# Power_w_tantalum.net
KiCad netlist of a schematic drawn in Altium Designer
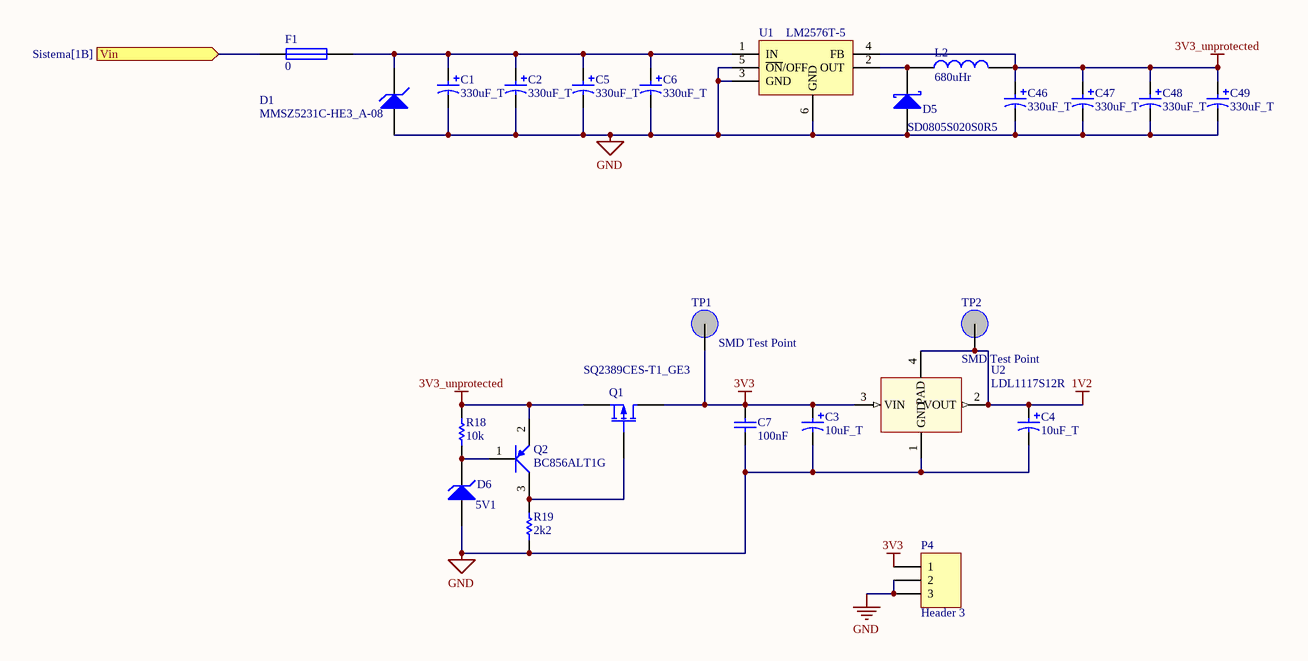
[diagram p0: Power_w_tantalum.SchDoc]

(export (version "E")
  (design (tool "Eeschema 10.0.6"))
  (components
    (comp (ref "C1")
      (value "330uF_T")
      (footprint "C_2917")
      (description "Capacitor SMD 2917 Tant")
      (fields
        (field (name "MANUFACTURER") "Vishay")
        (field (name "MANUFACTURER PART NUMBER") "TMCP1A106MTRF")
      )
      (libsource (lib "Mi_lib") (part "C_330uF_tant_16V"))
    )
    (comp (ref "C2")
      (value "330uF_T")
      (footprint "C_2917")
      (description "Capacitor SMD 2917 Tant")
      (fields
        (field (name "MANUFACTURER") "Vishay")
        (field (name "MANUFACTURER PART NUMBER") "TMCP1A106MTRF")
      )
      (libsource (lib "Mi_lib") (part "C_330uF_tant_16V"))
    )
    (comp (ref "C3")
      (value "10uF_T")
      (footprint "C_0805_2013_c")
      (description "Capacitor SMD 0805 Tant")
      (fields
        (field (name "MANUFACTURER") "Vishay")
        (field (name "MANUFACTURER PART NUMBER") "TMCP1A106MTRF")
      )
      (libsource (lib "MyLibraryV2") (part "C_10uF_10V_b"))
    )
    (comp (ref "C4")
      (value "10uF_T")
      (footprint "C_0805_2013_c")
      (description "Capacitor SMD 0805 Tant")
      (fields
        (field (name "MANUFACTURER") "Vishay")
        (field (name "MANUFACTURER PART NUMBER") "TMCP1A106MTRF")
      )
      (libsource (lib "MyLibraryV2") (part "C_10uF_10V_b"))
    )
    (comp (ref "C5")
      (value "330uF_T")
      (footprint "C_2917")
      (description "Capacitor SMD 2917 Tant")
      (fields
        (field (name "MANUFACTURER") "Vishay")
        (field (name "MANUFACTURER PART NUMBER") "TMCP1A106MTRF")
      )
      (libsource (lib "Mi_lib") (part "C_330uF_tant_16V"))
    )
    (comp (ref "C6")
      (value "330uF_T")
      (footprint "C_2917")
      (description "Capacitor SMD 2917 Tant")
      (fields
        (field (name "MANUFACTURER") "Vishay")
        (field (name "MANUFACTURER PART NUMBER") "TMCP1A106MTRF")
      )
      (libsource (lib "Mi_lib") (part "C_330uF_tant_16V"))
    )
    (comp (ref "C7")
      (value "100nF")
      (footprint "C_0805_2013_b")
      (description "Capacitor SMD 0805")
      (fields (field (name "TOLERANCE") "10%") (field (name "VOLTAGE") "50V"))
      (libsource (lib "MyLibraryV2") (part "C_100nF_50V_b"))
    )
    (comp (ref "C46")
      (value "330uF_T")
      (footprint "C_2917")
      (description "Capacitor SMD 2917 Tant")
      (fields
        (field (name "MANUFACTURER") "Vishay")
        (field (name "MANUFACTURER PART NUMBER") "TMCP1A106MTRF")
      )
      (libsource (lib "Mi_lib") (part "C_330uF_tant_16V"))
    )
    (comp (ref "C47")
      (value "330uF_T")
      (footprint "C_2917")
      (description "Capacitor SMD 2917 Tant")
      (fields
        (field (name "MANUFACTURER") "Vishay")
        (field (name "MANUFACTURER PART NUMBER") "TMCP1A106MTRF")
      )
      (libsource (lib "Mi_lib") (part "C_330uF_tant_16V"))
    )
    (comp (ref "C48")
      (value "330uF_T")
      (footprint "C_2917")
      (description "Capacitor SMD 2917 Tant")
      (fields
        (field (name "MANUFACTURER") "Vishay")
        (field (name "MANUFACTURER PART NUMBER") "TMCP1A106MTRF")
      )
      (libsource (lib "Mi_lib") (part "C_330uF_tant_16V"))
    )
    (comp (ref "C49")
      (value "330uF_T")
      (footprint "C_2917")
      (description "Capacitor SMD 2917 Tant")
      (fields
        (field (name "MANUFACTURER") "Vishay")
        (field (name "MANUFACTURER PART NUMBER") "TMCP1A106MTRF")
      )
      (libsource (lib "Mi_lib") (part "C_330uF_tant_16V"))
    )
    (comp (ref "D1")
      (value "MMSZ5231C-HE3_A-08")
      (footprint "D_SOD-123")
      (description "Diode SMD SOD-123 Zener 5V1")
      (fields (field (name "TOLERANCE") "2%") (field (name "MANUFACTURER") "Vishay Semiconductors"))
      (libsource (lib "Mi_lib") (part "D_MMSZ5231C-HE3_A-08"))
    )
    (comp (ref "D5")
      (value "SD0805S020S0R5")
      (footprint "D_SOD-123")
      (description "Diode SMD D_SD0805S020S0R5")
      (fields (field (name "MANUFACTURER") "Diodes") (field (name "MANUFACTURER PART NUMBER") "B550C-13-F"))
      (libsource (lib "Mi_lib") (part "D_SD0805S020S0R5"))
    )
    (comp (ref "D6")
      (value "5V1")
      (footprint "D_SOD-123")
      (description "Zener Diode")
      (fields (field (name "TOLERANCE") "3%") (field (name "MANUFACTURER") "Diodes"))
      (libsource (lib "MyLibraryV2") (part "D_DDZ5V1B-7"))
    )
    (comp (ref "F1")
      (value "0")
      (footprint "F_0805_2012")
      (description "(Generico) Fuse SMD 0805")
      (fields (field (name "PUBLISHER") "Altium Limited"))
      (libsource (lib "MyLibraryV2") (part "F_?_0805"))
    )
    (comp (ref "L2")
      (value "680uHr")
      (footprint "L_SMD_10x10")
      (description "(Generico)  Inductor SMD 10x10")
      (libsource (lib "MyLibraryV2") (part "L_?_5"))
    )
    (comp (ref "P4")
      (value "Header 3")
      (footprint "P_HDR1X3_3D")
      (description "Header, 3-Pin")
      (libsource (lib "MyLibraryV2") (part "P_Header 3"))
    )
    (comp (ref "Q1")
      (value "SQ2389CES-T1_GE3")
      (footprint "Q_SOT-23")
      (libsource (lib "Mi_lib") (part "Q_SQ2389CES-T1_GE3"))
    )
    (comp (ref "Q2")
      (value "BC856ALT1G")
      (footprint "Q_SOT-23B_N")
      (description "TRANS PNP 65V 0.1A SOT23")
      (fields (field (name "MANUFACTURER") "ON Semiconductor"))
      (libsource (lib "MyLibraryV2") (part "Q_BC856"))
    )
    (comp (ref "R18")
      (value "10k")
      (footprint "R_0805_2012_a")
      (description "Resistor SMD 0805")
      (fields (field (name "TOLERANCE") "1%") (field (name "MANUFACTURER") "Yageo"))
      (libsource (lib "MyLibraryV2") (part "R_10k_b"))
    )
    (comp (ref "R19")
      (value "2k2")
      (footprint "R_0805_2012_a")
      (description "Resistor SMD 0805")
      (fields (field (name "TOLERANCE") "1%") (field (name "MANUFACTURER") "Bourns"))
      (libsource (lib "MyLibraryV2") (part "R_2k2_b"))
    )
    (comp (ref "TP1")
      (value "SMD Test Point")
      (footprint "TP SMD")
      (description "Test Point SMD")
      (fields (field (name "PUBLISHER") "Altium Limited"))
      (libsource (lib "MyLibraryV2") (part "P_T_TP"))
    )
    (comp (ref "TP2")
      (value "SMD Test Point")
      (footprint "TP SMD")
      (description "Test Point SMD")
      (fields (field (name "PUBLISHER") "Altium Limited"))
      (libsource (lib "MyLibraryV2") (part "P_T_TP"))
    )
    (comp (ref "U1")
      (value "LM2576T-5")
      (footprint "U_SMD_TO-263-5")
      (libsource (lib "MyLibraryV2") (part "U_LM2576-3.3WU"))
    )
    (comp (ref "U2")
      (value "LDL1117S12R")
      (footprint "U_SOT-223")
      (description "LDL1117 Series 1.2 A 2.5 V High PSRR LDO Linear Voltage Regulator-SOT-223")
      (fields
        (field (name "MANUFACTURER") "STMicroelectronics")
        (field (name "MANUFACTURER PART NUMBER") "LDL1117S25R")
      )
      (libsource (lib "MyLibraryV2") (part "U_LDL1117"))
    )
  )
  (nets
    (net (code "1") (name "/Vin") (class "Default")
      (node (ref "F1") (pin "1") (pinfunction "1_1") (pintype "passive"))
    )
    (net (code "2") (name "1V2") (class "Default")
      (node (ref "C4") (pin "1") (pinfunction "1_1") (pintype "passive"))
      (node (ref "TP2") (pin "1") (pinfunction "1_1") (pintype "passive"))
      (node (ref "U2") (pin "2") (pinfunction "VOUT_2") (pintype "output"))
      (node (ref "U2") (pin "4") (pinfunction "PAD_4") (pintype "passive"))
    )
    (net (code "3") (name "3V3") (class "Default")
      (node (ref "C3") (pin "1") (pinfunction "1_1") (pintype "passive"))
      (node (ref "C7") (pin "2") (pinfunction "2_2") (pintype "passive"))
      (node (ref "P4") (pin "1") (pinfunction "1_1") (pintype "passive"))
      (node (ref "Q1") (pin "3") (pinfunction "D_3") (pintype "passive"))
      (node (ref "TP1") (pin "1") (pinfunction "1_1") (pintype "passive"))
      (node (ref "U2") (pin "3") (pinfunction "VIN_3") (pintype "input"))
    )
    (net (code "4") (name "3V3_unprotected") (class "Default")
      (node (ref "C46") (pin "1") (pinfunction "1_1") (pintype "passive"))
      (node (ref "C47") (pin "1") (pinfunction "1_1") (pintype "passive"))
      (node (ref "C48") (pin "1") (pinfunction "1_1") (pintype "passive"))
      (node (ref "C49") (pin "1") (pinfunction "1_1") (pintype "passive"))
      (node (ref "L2") (pin "2") (pinfunction "2_2") (pintype "passive"))
      (node (ref "Q1") (pin "2") (pinfunction "S_2") (pintype "passive"))
      (node (ref "Q2") (pin "2") (pinfunction "E_2") (pintype "passive"))
      (node (ref "R18") (pin "2") (pinfunction "2_2") (pintype "passive"))
      (node (ref "U1") (pin "4") (pinfunction "FB_4") (pintype "passive"))
    )
    (net (code "5") (name "GND") (class "Default")
      (node (ref "C1") (pin "2") (pinfunction "2_2") (pintype "passive"))
      (node (ref "C2") (pin "2") (pinfunction "2_2") (pintype "passive"))
      (node (ref "C3") (pin "2") (pinfunction "2_2") (pintype "passive"))
      (node (ref "C4") (pin "2") (pinfunction "2_2") (pintype "passive"))
      (node (ref "C46") (pin "2") (pinfunction "2_2") (pintype "passive"))
      (node (ref "C47") (pin "2") (pinfunction "2_2") (pintype "passive"))
      (node (ref "C48") (pin "2") (pinfunction "2_2") (pintype "passive"))
      (node (ref "C49") (pin "2") (pinfunction "2_2") (pintype "passive"))
      (node (ref "C5") (pin "2") (pinfunction "2_2") (pintype "passive"))
      (node (ref "C6") (pin "2") (pinfunction "2_2") (pintype "passive"))
      (node (ref "C7") (pin "1") (pinfunction "1_1") (pintype "passive"))
      (node (ref "D1") (pin "2") (pinfunction "A_2") (pintype "passive"))
      (node (ref "D5") (pin "2") (pinfunction "A_2") (pintype "passive"))
      (node (ref "D6") (pin "2") (pinfunction "A_2") (pintype "passive"))
      (node (ref "P4") (pin "2") (pinfunction "2_2") (pintype "passive"))
      (node (ref "P4") (pin "3") (pinfunction "3_3") (pintype "passive"))
      (node (ref "R19") (pin "2") (pinfunction "2_2") (pintype "passive"))
      (node (ref "U1") (pin "3") (pinfunction "GND_3") (pintype "passive"))
      (node (ref "U1") (pin "5") (pinfunction "~{ON}/OFF_5") (pintype "passive"))
      (node (ref "U1") (pin "6") (pinfunction "GND_6") (pintype "passive"))
      (node (ref "U2") (pin "1") (pinfunction "GND_1") (pintype "power_in"))
    )
    (net (code "6") (name "Net-(D1-K)") (class "Default")
      (node (ref "C1") (pin "1") (pinfunction "1_1") (pintype "passive"))
      (node (ref "C2") (pin "1") (pinfunction "1_1") (pintype "passive"))
      (node (ref "C5") (pin "1") (pinfunction "1_1") (pintype "passive"))
      (node (ref "C6") (pin "1") (pinfunction "1_1") (pintype "passive"))
      (node (ref "D1") (pin "1") (pinfunction "K_1") (pintype "passive"))
      (node (ref "F1") (pin "2") (pinfunction "2_2") (pintype "passive"))
      (node (ref "U1") (pin "1") (pinfunction "IN_1") (pintype "passive"))
    )
    (net (code "7") (name "Net-(D5-K)") (class "Default")
      (node (ref "D5") (pin "1") (pinfunction "K_1") (pintype "passive"))
      (node (ref "L2") (pin "1") (pinfunction "1_1") (pintype "passive"))
      (node (ref "U1") (pin "2") (pinfunction "OUT_2") (pintype "passive"))
    )
    (net (code "8") (name "Net-(D6-K)") (class "Default")
      (node (ref "D6") (pin "1") (pinfunction "K_1") (pintype "passive"))
      (node (ref "Q2") (pin "1") (pinfunction "B_1") (pintype "passive"))
      (node (ref "R18") (pin "1") (pinfunction "1_1") (pintype "passive"))
    )
    (net (code "9") (name "Net-(Q1-G)") (class "Default")
      (node (ref "Q1") (pin "1") (pinfunction "G_1") (pintype "passive"))
      (node (ref "Q2") (pin "3") (pinfunction "C_3") (pintype "passive"))
      (node (ref "R19") (pin "1") (pinfunction "1_1") (pintype "passive"))
    )
  )
)
